# HT62N.net
KiCad netlist of a schematic drawn in Altium Designer
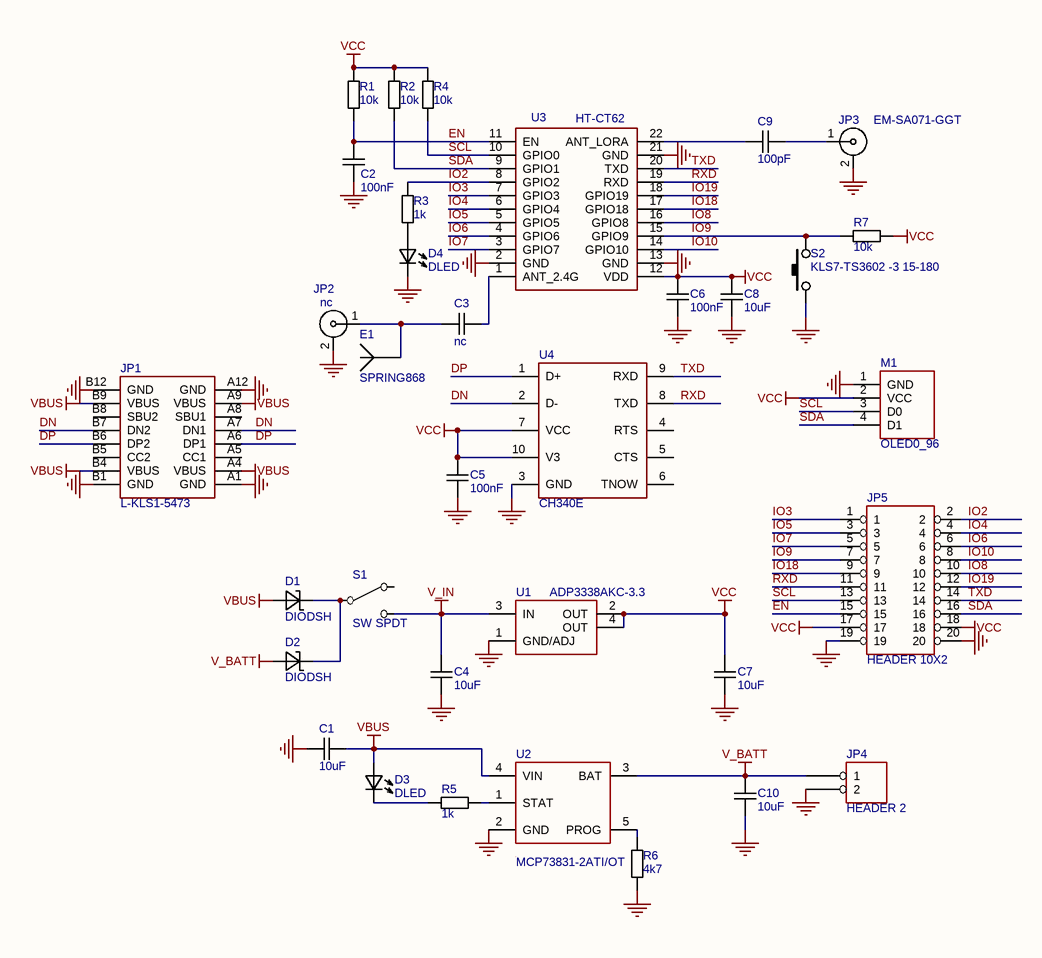
[diagram p0: HT62N.SchDoc]

(export (version "E")
  (design (tool "Eeschema 10.0.6"))
  (components
    (comp (ref "C1")
      (value "10uF")
      (footprint "C-0805")
      (fields (field (name "VOLTAGE") "50V"))
      (libsource (lib "Passive") (part "CAPN"))
    )
    (comp (ref "C2")
      (value "100nF")
      (footprint "C-0603")
      (fields (field (name "VOLTAGE") "50V"))
      (libsource (lib "Passive") (part "CAPN"))
    )
    (comp (ref "C3")
      (value "nc")
      (footprint "C-0603")
      (fields (field (name "VOLTAGE") "50V"))
      (libsource (lib "Passive") (part "CAPN"))
    )
    (comp (ref "C4")
      (value "10uF")
      (footprint "C-0805")
      (fields (field (name "VOLTAGE") "50V"))
      (libsource (lib "Passive") (part "CAPN"))
    )
    (comp (ref "C5")
      (value "100nF")
      (footprint "C-0603")
      (fields (field (name "VOLTAGE") "50V"))
      (libsource (lib "Passive") (part "CAPN"))
    )
    (comp (ref "C6")
      (value "100nF")
      (footprint "C-0603")
      (fields (field (name "VOLTAGE") "50V"))
      (libsource (lib "Passive") (part "CAPN"))
    )
    (comp (ref "C7")
      (value "10uF")
      (footprint "C-0805")
      (fields (field (name "VOLTAGE") "50V"))
      (libsource (lib "Passive") (part "CAPN"))
    )
    (comp (ref "C8")
      (value "10uF")
      (footprint "C-0805")
      (fields (field (name "VOLTAGE") "50V"))
      (libsource (lib "Passive") (part "CAPN"))
    )
    (comp (ref "C9")
      (value "100pF")
      (footprint "C-0603")
      (fields (field (name "VOLTAGE") "50V"))
      (libsource (lib "Passive") (part "CAPN"))
    )
    (comp (ref "C10")
      (value "10uF")
      (footprint "C-0805")
      (fields (field (name "VOLTAGE") "50V"))
      (libsource (lib "Passive") (part "CAPN"))
    )
    (comp (ref "D1") (value "DIODSH") (footprint "D-SMA") (libsource (lib "Diodes") (part "DIODSH")))
    (comp (ref "D2") (value "DIODSH") (footprint "D-SMA") (libsource (lib "Diodes") (part "DIODSH")))
    (comp (ref "D3") (value "DLED") (footprint "LED_3mm_RED") (libsource (lib "Diodes") (part "DLED")))
    (comp (ref "D4") (value "DLED") (footprint "LED_3mm_RED") (libsource (lib "Diodes") (part "DLED")))
    (comp (ref "E1") (value "SPRING868") (footprint "ANT_H868_V") (libsource (lib "Passive") (part "ANT")))
    (comp (ref "JP1")
      (value "L-KLS1-5473")
      (footprint "USB_C_SMD_SLOT")
      (libsource (lib "Connectors") (part "L-KLS1-5473"))
    )
    (comp (ref "JP2")
      (value "nc")
      (footprint "SMA_F_EDGE")
      (description "SMA Female R/A PCB Mount")
      (libsource (lib "Connectors") (part "SMA"))
    )
    (comp (ref "JP3")
      (value "EM-SA071-GGT")
      (footprint "SMA_F_EDGE")
      (description "SMA Female R/A PCB Mount")
      (libsource (lib "Connectors") (part "SMA"))
    )
    (comp (ref "JP4")
      (value "HEADER 2")
      (footprint "PLS1-2")
      (libsource (lib "Connectors") (part "HEADER 2"))
    )
    (comp (ref "JP5")
      (value "HEADER 10X2")
      (footprint "PLS2_10")
      (libsource (lib "Connectors") (part "HEADER 10X2"))
    )
    (comp (ref "M1")
      (value "OLED0_96")
      (footprint "OLED096_I2C")
      (libsource (lib "RFmodules") (part "OLED0_96_I2C"))
    )
    (comp (ref "R1") (value "10k") (footprint "R-0603") (libsource (lib "Passive") (part "RES")))
    (comp (ref "R2") (value "10k") (footprint "R-0603") (libsource (lib "Passive") (part "RES")))
    (comp (ref "R3") (value "1k") (footprint "R-0603") (libsource (lib "") (part "RES_2")))
    (comp (ref "R4") (value "10k") (footprint "R-0603") (libsource (lib "Passive") (part "RES")))
    (comp (ref "R5") (value "1k") (footprint "R-0603") (libsource (lib "") (part "RES_1")))
    (comp (ref "R6") (value "4k7") (footprint "R-0603") (libsource (lib "") (part "RES_2")))
    (comp (ref "R7") (value "10k") (footprint "R-0603") (libsource (lib "") (part "RES_1")))
    (comp (ref "S1")
      (value "SW SPDT")
      (footprint "SK-12D07VG5")
      (libsource (lib "Switches") (part "SW SPDT"))
    )
    (comp (ref "S2")
      (value "KLS7-TS3602 -3 15-180")
      (footprint "KLS7-TS3602")
      (libsource (lib "Switches") (part "SW-1"))
    )
    (comp (ref "U1")
      (value "ADP3338AKC-3.3")
      (footprint "SOT223")
      (description "LOW CURRENT ADJUSTABLE  VOLTAGE REGULATOR")
      (libsource (lib "ICs") (part "LDL1117"))
    )
    (comp (ref "U2")
      (value "MCP73831-2ATI/OT")
      (footprint "SOT-23-5")
      (fields
        (field (name "LIBRARY PART") "IC`s.SchLib")
        (field (name "FOOTPRINT PART") "IC-package.PcbLib")
        (field (name "MANUFACTURER") "Texas Instruments")
      )
      (libsource (lib "ICs") (part "MCP73831-2ATI/OT"))
    )
    (comp (ref "U3") (value "HT-CT62") (footprint "HT-CT62") (libsource (lib "RFmodules") (part "HT-CT62")))
    (comp (ref "U4") (value "CH340E") (footprint "MSOP-10") (libsource (lib "ICs") (part "CH340E")))
  )
  (nets
    (net (code "1") (name "/DN") (class "Default")
      (node (ref "JP1") (pin "A7") (pinfunction "DN1_A7") (pintype "passive"))
      (node (ref "JP1") (pin "B7") (pinfunction "DN2_B7") (pintype "passive"))
      (node (ref "U4") (pin "2") (pinfunction "D-_2") (pintype "passive"))
    )
    (net (code "2") (name "/DP") (class "Default")
      (node (ref "JP1") (pin "A6") (pinfunction "DP1_A6") (pintype "passive"))
      (node (ref "JP1") (pin "B6") (pinfunction "DP2_B6") (pintype "passive"))
      (node (ref "U4") (pin "1") (pinfunction "D+_1") (pintype "passive"))
    )
    (net (code "3") (name "/EN") (class "Default")
      (node (ref "C2") (pin "2") (pinfunction "2_2") (pintype "passive"))
      (node (ref "JP5") (pin "15") (pinfunction "15_15") (pintype "passive"))
      (node (ref "R1") (pin "2") (pinfunction "2_2") (pintype "passive"))
      (node (ref "U3") (pin "11") (pinfunction "EN_11") (pintype "passive"))
    )
    (net (code "4") (name "/IO2") (class "Default")
      (node (ref "JP5") (pin "2") (pinfunction "2_2") (pintype "passive"))
      (node (ref "R3") (pin "2") (pinfunction "2_2") (pintype "passive"))
      (node (ref "U3") (pin "8") (pinfunction "GPIO2_8") (pintype "passive"))
    )
    (net (code "5") (name "/IO3") (class "Default")
      (node (ref "JP5") (pin "1") (pinfunction "1_1") (pintype "passive"))
      (node (ref "U3") (pin "7") (pinfunction "GPIO3_7") (pintype "passive"))
    )
    (net (code "6") (name "/IO4") (class "Default")
      (node (ref "JP5") (pin "4") (pinfunction "4_4") (pintype "passive"))
      (node (ref "U3") (pin "6") (pinfunction "GPIO4_6") (pintype "passive"))
    )
    (net (code "7") (name "/IO5") (class "Default")
      (node (ref "JP5") (pin "3") (pinfunction "3_3") (pintype "passive"))
      (node (ref "U3") (pin "5") (pinfunction "GPIO5_5") (pintype "passive"))
    )
    (net (code "8") (name "/IO6") (class "Default")
      (node (ref "JP5") (pin "6") (pinfunction "6_6") (pintype "passive"))
      (node (ref "U3") (pin "4") (pinfunction "GPIO6_4") (pintype "passive"))
    )
    (net (code "9") (name "/IO7") (class "Default")
      (node (ref "JP5") (pin "5") (pinfunction "5_5") (pintype "passive"))
      (node (ref "U3") (pin "3") (pinfunction "GPIO7_3") (pintype "passive"))
    )
    (net (code "10") (name "/IO8") (class "Default")
      (node (ref "JP5") (pin "10") (pinfunction "10_10") (pintype "passive"))
      (node (ref "U3") (pin "16") (pinfunction "GPIO8_16") (pintype "passive"))
    )
    (net (code "11") (name "/IO9") (class "Default")
      (node (ref "JP5") (pin "7") (pinfunction "7_7") (pintype "passive"))
      (node (ref "R7") (pin "2") (pinfunction "2_2") (pintype "passive"))
      (node (ref "S2") (pin "2") (pinfunction "2_2") (pintype "passive"))
      (node (ref "U3") (pin "15") (pinfunction "GPIO9_15") (pintype "passive"))
    )
    (net (code "12") (name "/IO10") (class "Default")
      (node (ref "JP5") (pin "8") (pinfunction "8_8") (pintype "passive"))
      (node (ref "U3") (pin "14") (pinfunction "GPIO10_14") (pintype "passive"))
    )
    (net (code "13") (name "/IO18") (class "Default")
      (node (ref "JP5") (pin "9") (pinfunction "9_9") (pintype "passive"))
      (node (ref "U3") (pin "17") (pinfunction "GPIO18_17") (pintype "passive"))
    )
    (net (code "14") (name "/IO19") (class "Default")
      (node (ref "JP5") (pin "12") (pinfunction "12_12") (pintype "passive"))
      (node (ref "U3") (pin "18") (pinfunction "GPIO19_18") (pintype "passive"))
    )
    (net (code "15") (name "/RXD") (class "Default")
      (node (ref "JP5") (pin "11") (pinfunction "11_11") (pintype "passive"))
      (node (ref "U3") (pin "19") (pinfunction "RXD_19") (pintype "passive"))
      (node (ref "U4") (pin "8") (pinfunction "TXD_8") (pintype "passive"))
    )
    (net (code "16") (name "/SCL") (class "Default")
      (node (ref "JP5") (pin "13") (pinfunction "13_13") (pintype "passive"))
      (node (ref "M1") (pin "3") (pinfunction "D0_3") (pintype "passive"))
      (node (ref "R4") (pin "2") (pinfunction "2_2") (pintype "passive"))
      (node (ref "U3") (pin "10") (pinfunction "GPIO0_10") (pintype "passive"))
    )
    (net (code "17") (name "/SDA") (class "Default")
      (node (ref "JP5") (pin "16") (pinfunction "16_16") (pintype "passive"))
      (node (ref "M1") (pin "4") (pinfunction "D1_4") (pintype "passive"))
      (node (ref "R2") (pin "2") (pinfunction "2_2") (pintype "passive"))
      (node (ref "U3") (pin "9") (pinfunction "GPIO1_9") (pintype "passive"))
    )
    (net (code "18") (name "/TXD") (class "Default")
      (node (ref "JP5") (pin "14") (pinfunction "14_14") (pintype "passive"))
      (node (ref "U3") (pin "20") (pinfunction "TXD_20") (pintype "passive"))
      (node (ref "U4") (pin "9") (pinfunction "RXD_9") (pintype "passive"))
    )
    (net (code "19") (name "GND") (class "Default")
      (node (ref "C1") (pin "1") (pinfunction "1_1") (pintype "passive"))
      (node (ref "C10") (pin "1") (pinfunction "1_1") (pintype "passive"))
      (node (ref "C2") (pin "1") (pinfunction "1_1") (pintype "passive"))
      (node (ref "C4") (pin "2") (pinfunction "2_2") (pintype "passive"))
      (node (ref "C5") (pin "1") (pinfunction "1_1") (pintype "passive"))
      (node (ref "C6") (pin "1") (pinfunction "1_1") (pintype "passive"))
      (node (ref "C7") (pin "2") (pinfunction "2_2") (pintype "passive"))
      (node (ref "C8") (pin "2") (pinfunction "2_2") (pintype "passive"))
      (node (ref "D4") (pin "2") (pinfunction "2_2") (pintype "passive"))
      (node (ref "JP1") (pin "A1") (pinfunction "GND_A1") (pintype "passive"))
      (node (ref "JP1") (pin "A12") (pinfunction "GND_A12") (pintype "passive"))
      (node (ref "JP1") (pin "B1") (pinfunction "GND_B1") (pintype "passive"))
      (node (ref "JP1") (pin "B12") (pinfunction "GND_B12") (pintype "passive"))
      (node (ref "JP2") (pin "2") (pinfunction "2_2") (pintype "passive"))
      (node (ref "JP3") (pin "2") (pinfunction "2_2") (pintype "passive"))
      (node (ref "JP4") (pin "2") (pinfunction "2_2") (pintype "passive"))
      (node (ref "JP5") (pin "19") (pinfunction "19_19") (pintype "passive"))
      (node (ref "JP5") (pin "20") (pinfunction "20_20") (pintype "passive"))
      (node (ref "M1") (pin "1") (pinfunction "GND_1") (pintype "passive"))
      (node (ref "R6") (pin "1") (pinfunction "1_1") (pintype "passive"))
      (node (ref "S2") (pin "1") (pinfunction "1_1") (pintype "passive"))
      (node (ref "U1") (pin "1") (pinfunction "GND/ADJ_1") (pintype "power_in"))
      (node (ref "U2") (pin "2") (pinfunction "GND_2") (pintype "passive"))
      (node (ref "U3") (pin "13") (pinfunction "GND_13") (pintype "passive"))
      (node (ref "U3") (pin "2") (pinfunction "GND_2") (pintype "passive"))
      (node (ref "U3") (pin "21") (pinfunction "GND_21") (pintype "passive"))
      (node (ref "U4") (pin "3") (pinfunction "GND_3") (pintype "passive"))
    )
    (net (code "20") (name "Net-(C3-Pad1)") (class "Default")
      (node (ref "C3") (pin "1") (pinfunction "1_1") (pintype "passive"))
      (node (ref "E1") (pin "1") (pinfunction "1_1") (pintype "passive"))
      (node (ref "JP2") (pin "1") (pinfunction "1_1") (pintype "passive"))
    )
    (net (code "21") (name "Net-(C9-Pad2)") (class "Default")
      (node (ref "C9") (pin "2") (pinfunction "2_2") (pintype "passive"))
      (node (ref "JP3") (pin "1") (pinfunction "1_1") (pintype "passive"))
    )
    (net (code "22") (name "Net-(D3-Pad2)") (class "Default")
      (node (ref "D3") (pin "2") (pinfunction "2_2") (pintype "passive"))
      (node (ref "R5") (pin "2") (pinfunction "2_2") (pintype "passive"))
    )
    (net (code "23") (name "Net-(D4-Pad1)") (class "Default")
      (node (ref "D4") (pin "1") (pinfunction "1_1") (pintype "passive"))
      (node (ref "R3") (pin "1") (pinfunction "1_1") (pintype "passive"))
    )
    (net (code "24") (name "Net-(S1-COMMON)") (class "Default")
      (node (ref "D1") (pin "2") (pinfunction "2_2") (pintype "passive"))
      (node (ref "D2") (pin "2") (pinfunction "2_2") (pintype "passive"))
      (node (ref "S1") (pin "2") (pinfunction "COMMON_2") (pintype "passive"))
    )
    (net (code "25") (name "Net-(U2-PROG)") (class "Default")
      (node (ref "R6") (pin "2") (pinfunction "2_2") (pintype "passive"))
      (node (ref "U2") (pin "5") (pinfunction "PROG_5") (pintype "passive"))
    )
    (net (code "26") (name "Net-(U2-STAT)") (class "Default")
      (node (ref "R5") (pin "1") (pinfunction "1_1") (pintype "passive"))
      (node (ref "U2") (pin "1") (pinfunction "STAT_1") (pintype "passive"))
    )
    (net (code "27") (name "Net-(U3-ANT_2.4G)") (class "Default")
      (node (ref "C3") (pin "2") (pinfunction "2_2") (pintype "passive"))
      (node (ref "U3") (pin "1") (pinfunction "ANT_2.4G_1") (pintype "passive"))
    )
    (net (code "28") (name "Net-(U3-ANT_LORA)") (class "Default")
      (node (ref "C9") (pin "1") (pinfunction "1_1") (pintype "passive"))
      (node (ref "U3") (pin "22") (pinfunction "ANT_LORA_22") (pintype "passive"))
    )
    (net (code "29") (name "VBUS") (class "Default")
      (node (ref "C1") (pin "2") (pinfunction "2_2") (pintype "passive"))
      (node (ref "D1") (pin "1") (pinfunction "1_1") (pintype "passive"))
      (node (ref "D3") (pin "1") (pinfunction "1_1") (pintype "passive"))
      (node (ref "JP1") (pin "A4") (pinfunction "VBUS_A4") (pintype "passive"))
      (node (ref "JP1") (pin "A9") (pinfunction "VBUS_A9") (pintype "passive"))
      (node (ref "JP1") (pin "B4") (pinfunction "VBUS_B4") (pintype "passive"))
      (node (ref "JP1") (pin "B9") (pinfunction "VBUS_B9") (pintype "passive"))
      (node (ref "U2") (pin "4") (pinfunction "VIN_4") (pintype "passive"))
    )
    (net (code "30") (name "VCC") (class "Default")
      (node (ref "C5") (pin "2") (pinfunction "2_2") (pintype "passive"))
      (node (ref "C6") (pin "2") (pinfunction "2_2") (pintype "passive"))
      (node (ref "C7") (pin "1") (pinfunction "1_1") (pintype "passive"))
      (node (ref "C8") (pin "1") (pinfunction "1_1") (pintype "passive"))
      (node (ref "JP5") (pin "17") (pinfunction "17_17") (pintype "passive"))
      (node (ref "JP5") (pin "18") (pinfunction "18_18") (pintype "passive"))
      (node (ref "M1") (pin "2") (pinfunction "VCC_2") (pintype "passive"))
      (node (ref "R1") (pin "1") (pinfunction "1_1") (pintype "passive"))
      (node (ref "R2") (pin "1") (pinfunction "1_1") (pintype "passive"))
      (node (ref "R4") (pin "1") (pinfunction "1_1") (pintype "passive"))
      (node (ref "R7") (pin "1") (pinfunction "1_1") (pintype "passive"))
      (node (ref "U1") (pin "2") (pinfunction "OUT_2") (pintype "power_in"))
      (node (ref "U1") (pin "4") (pinfunction "OUT_4") (pintype "power_in"))
      (node (ref "U3") (pin "12") (pinfunction "VDD_12") (pintype "passive"))
      (node (ref "U4") (pin "10") (pinfunction "V3_10") (pintype "passive"))
      (node (ref "U4") (pin "7") (pinfunction "VCC_7") (pintype "passive"))
    )
    (net (code "31") (name "VSS") (class "Default")
      (node (ref "JP1") (pin "17") (pinfunction "VSS_17") (pintype "power_in"))
    )
    (net (code "32") (name "V_BATT") (class "Default")
      (node (ref "C10") (pin "2") (pinfunction "2_2") (pintype "passive"))
      (node (ref "D2") (pin "1") (pinfunction "1_1") (pintype "passive"))
      (node (ref "JP4") (pin "1") (pinfunction "1_1") (pintype "passive"))
      (node (ref "U2") (pin "3") (pinfunction "BAT_3") (pintype "passive"))
    )
    (net (code "33") (name "V_IN") (class "Default")
      (node (ref "C4") (pin "1") (pinfunction "1_1") (pintype "passive"))
      (node (ref "S1") (pin "3") (pinfunction "NO_3") (pintype "passive"))
      (node (ref "U1") (pin "3") (pinfunction "IN_3") (pintype "power_in"))
    )
    (net (code "34") (name "unconnected-(JP1-CC1-PadA5)") (class "Default")
      (node (ref "JP1") (pin "A5") (pinfunction "CC1_A5") (pintype "passive"))
    )
    (net (code "35") (name "unconnected-(JP1-CC2-PadB5)") (class "Default")
      (node (ref "JP1") (pin "B5") (pinfunction "CC2_B5") (pintype "passive"))
    )
    (net (code "36") (name "unconnected-(JP1-SBU1-PadA8)") (class "Default")
      (node (ref "JP1") (pin "A8") (pinfunction "SBU1_A8") (pintype "passive"))
    )
    (net (code "37") (name "unconnected-(JP1-SBU2-PadB8)") (class "Default")
      (node (ref "JP1") (pin "B8") (pinfunction "SBU2_B8") (pintype "passive"))
    )
    (net (code "38") (name "unconnected-(S1-NC-Pad1)") (class "Default")
      (node (ref "S1") (pin "1") (pinfunction "NC_1") (pintype "passive"))
    )
    (net (code "39") (name "unconnected-(U4-CTS-Pad5)") (class "Default")
      (node (ref "U4") (pin "5") (pinfunction "CTS_5") (pintype "passive"))
    )
    (net (code "40") (name "unconnected-(U4-RTS-Pad4)") (class "Default")
      (node (ref "U4") (pin "4") (pinfunction "RTS_4") (pintype "passive"))
    )
    (net (code "41") (name "unconnected-(U4-TNOW-Pad6)") (class "Default")
      (node (ref "U4") (pin "6") (pinfunction "TNOW_6") (pintype "passive"))
    )
  )
)
